# LC_BigOne_-_165_SerialIn_Register.net
KiCad netlist of a schematic drawn in Altium Designer
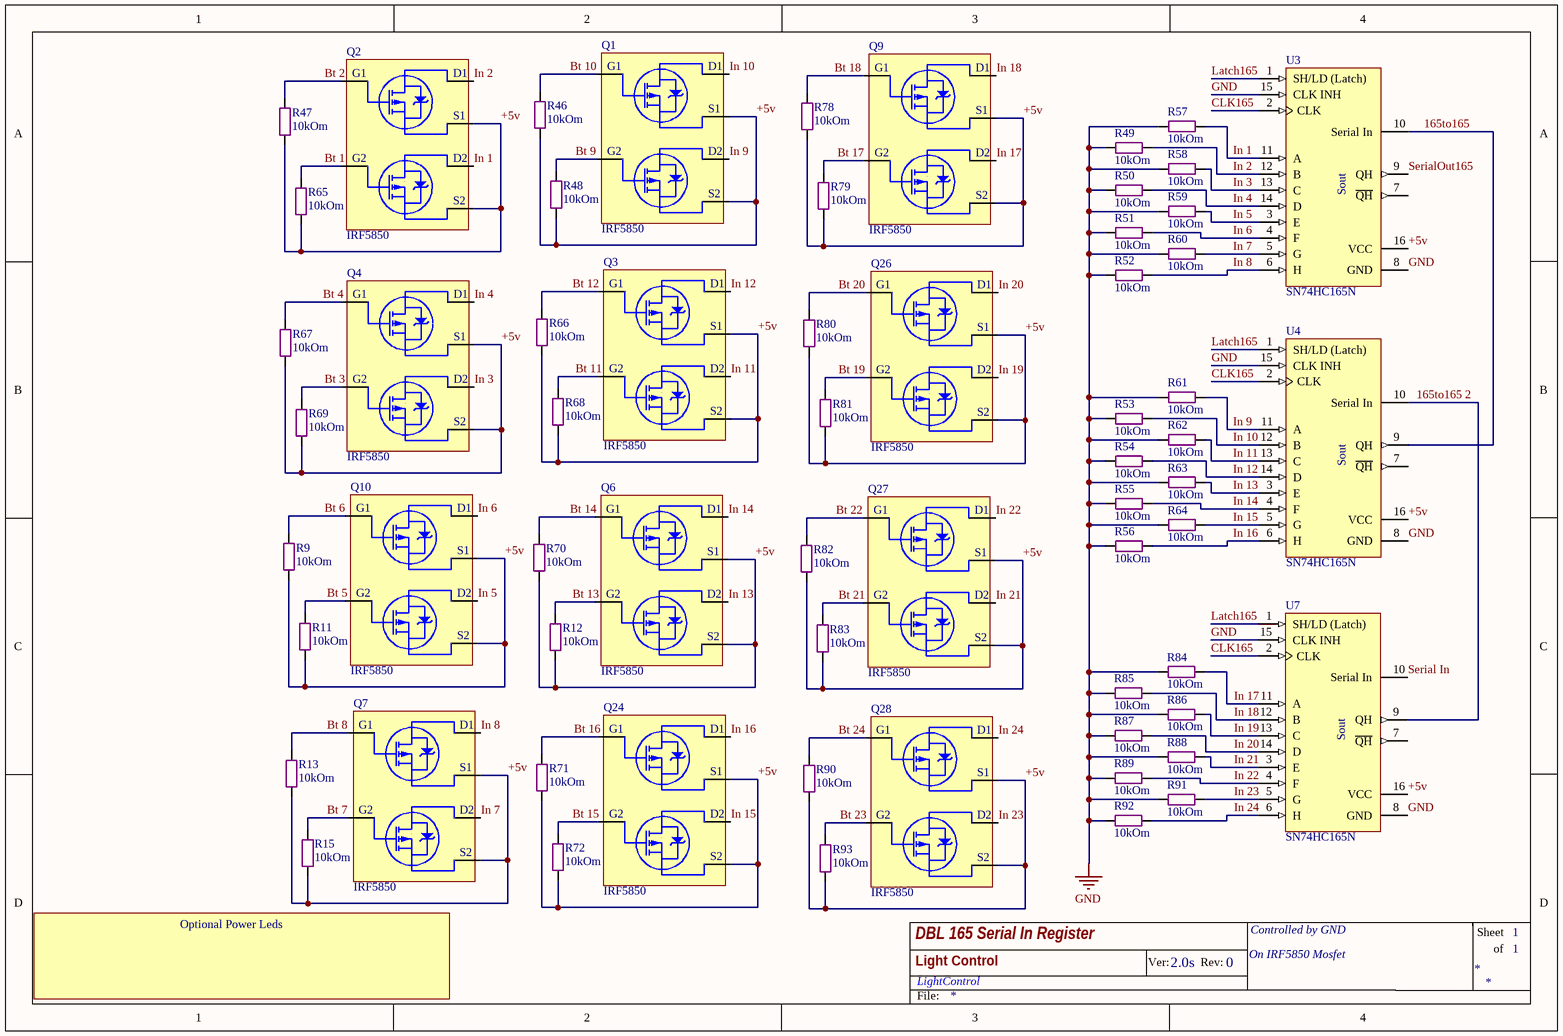
[diagram p0: LC BigOne - 165 SerialIn Register (v2).SchDoc]

(export (version "E")
  (design (tool "Eeschema 10.0.6"))
  (components
    (comp (ref "Q1")
      (value "IRF5850")
      (footprint "GeneralCases:TSOP-6")
      (description "Dual P-Ch  20V - 0.135Ω - 2.2A")
      (libsource (lib "Transistor") (part "IRF5850"))
    )
    (comp (ref "Q2")
      (value "IRF5850")
      (footprint "GeneralCases:TSOP-6")
      (description "Dual P-Ch  20V - 0.135Ω - 2.2A")
      (libsource (lib "Transistor") (part "IRF5850"))
    )
    (comp (ref "Q3")
      (value "IRF5850")
      (footprint "GeneralCases:TSOP-6")
      (description "Dual P-Ch  20V - 0.135Ω - 2.2A")
      (libsource (lib "Transistor") (part "IRF5850"))
    )
    (comp (ref "Q4")
      (value "IRF5850")
      (footprint "GeneralCases:TSOP-6")
      (description "Dual P-Ch  20V - 0.135Ω - 2.2A")
      (libsource (lib "Transistor") (part "IRF5850"))
    )
    (comp (ref "Q6")
      (value "IRF5850")
      (footprint "GeneralCases:TSOP-6")
      (description "Dual P-Ch  20V - 0.135Ω - 2.2A")
      (libsource (lib "Transistor") (part "IRF5850"))
    )
    (comp (ref "Q7")
      (value "IRF5850")
      (footprint "GeneralCases:TSOP-6")
      (description "Dual P-Ch  20V - 0.135Ω - 2.2A")
      (libsource (lib "Transistor") (part "IRF5850"))
    )
    (comp (ref "Q9")
      (value "IRF5850")
      (footprint "GeneralCases:TSOP-6")
      (description "Dual P-Ch  20V - 0.135Ω - 2.2A")
      (libsource (lib "Transistor") (part "IRF5850"))
    )
    (comp (ref "Q10")
      (value "IRF5850")
      (footprint "GeneralCases:TSOP-6")
      (description "Dual P-Ch  20V - 0.135Ω - 2.2A")
      (libsource (lib "Transistor") (part "IRF5850"))
    )
    (comp (ref "Q24")
      (value "IRF5850")
      (footprint "GeneralCases:TSOP-6")
      (description "Dual P-Ch  20V - 0.135Ω - 2.2A")
      (libsource (lib "Transistor") (part "IRF5850"))
    )
    (comp (ref "Q26")
      (value "IRF5850")
      (footprint "GeneralCases:TSOP-6")
      (description "Dual P-Ch  20V - 0.135Ω - 2.2A")
      (libsource (lib "Transistor") (part "IRF5850"))
    )
    (comp (ref "Q27")
      (value "IRF5850")
      (footprint "GeneralCases:TSOP-6")
      (description "Dual P-Ch  20V - 0.135Ω - 2.2A")
      (libsource (lib "Transistor") (part "IRF5850"))
    )
    (comp (ref "Q28")
      (value "IRF5850")
      (footprint "GeneralCases:TSOP-6")
      (description "Dual P-Ch  20V - 0.135Ω - 2.2A")
      (libsource (lib "Transistor") (part "IRF5850"))
    )
    (comp (ref "R9")
      (value "10kOm")
      (footprint "PassiveComponents:SMD 0805 (2012)")
      (libsource (lib "PassiveComponents") (part "Res All Types"))
    )
    (comp (ref "R11")
      (value "10kOm")
      (footprint "PassiveComponents:SMD 0805 (2012)")
      (libsource (lib "PassiveComponents") (part "Res All Types"))
    )
    (comp (ref "R12")
      (value "10kOm")
      (footprint "PassiveComponents:SMD 0805 (2012)")
      (libsource (lib "PassiveComponents") (part "Res All Types"))
    )
    (comp (ref "R13")
      (value "10kOm")
      (footprint "PassiveComponents:SMD 0805 (2012)")
      (libsource (lib "PassiveComponents") (part "Res All Types"))
    )
    (comp (ref "R15")
      (value "10kOm")
      (footprint "PassiveComponents:SMD 0805 (2012)")
      (libsource (lib "PassiveComponents") (part "Res All Types"))
    )
    (comp (ref "R46")
      (value "10kOm")
      (footprint "PassiveComponents:SMD 0805 (2012)")
      (libsource (lib "PassiveComponents") (part "Res All Types"))
    )
    (comp (ref "R47")
      (value "10kOm")
      (footprint "PassiveComponents:SMD 0805 (2012)")
      (libsource (lib "PassiveComponents") (part "Res All Types"))
    )
    (comp (ref "R48")
      (value "10kOm")
      (footprint "PassiveComponents:SMD 0805 (2012)")
      (libsource (lib "PassiveComponents") (part "Res All Types"))
    )
    (comp (ref "R49")
      (value "10kOm")
      (footprint "PassiveComponents:SMD 0805 (2012)")
      (libsource (lib "PassiveComponents") (part "Res All Types"))
    )
    (comp (ref "R50")
      (value "10kOm")
      (footprint "PassiveComponents:SMD 0805 (2012)")
      (libsource (lib "PassiveComponents") (part "Res All Types"))
    )
    (comp (ref "R51")
      (value "10kOm")
      (footprint "PassiveComponents:SMD 0805 (2012)")
      (libsource (lib "PassiveComponents") (part "Res All Types"))
    )
    (comp (ref "R52")
      (value "10kOm")
      (footprint "PassiveComponents:SMD 0805 (2012)")
      (libsource (lib "PassiveComponents") (part "Res All Types"))
    )
    (comp (ref "R53")
      (value "10kOm")
      (footprint "PassiveComponents:SMD 0805 (2012)")
      (libsource (lib "PassiveComponents") (part "Res All Types"))
    )
    (comp (ref "R54")
      (value "10kOm")
      (footprint "PassiveComponents:SMD 0805 (2012)")
      (libsource (lib "PassiveComponents") (part "Res All Types"))
    )
    (comp (ref "R55")
      (value "10kOm")
      (footprint "PassiveComponents:SMD 0805 (2012)")
      (libsource (lib "PassiveComponents") (part "Res All Types"))
    )
    (comp (ref "R56")
      (value "10kOm")
      (footprint "PassiveComponents:SMD 0805 (2012)")
      (libsource (lib "PassiveComponents") (part "Res All Types"))
    )
    (comp (ref "R57")
      (value "10kOm")
      (footprint "PassiveComponents:SMD 0805 (2012)")
      (libsource (lib "PassiveComponents") (part "Res All Types"))
    )
    (comp (ref "R58")
      (value "10kOm")
      (footprint "PassiveComponents:SMD 0805 (2012)")
      (libsource (lib "PassiveComponents") (part "Res All Types"))
    )
    (comp (ref "R59")
      (value "10kOm")
      (footprint "PassiveComponents:SMD 0805 (2012)")
      (libsource (lib "PassiveComponents") (part "Res All Types"))
    )
    (comp (ref "R60")
      (value "10kOm")
      (footprint "PassiveComponents:SMD 0805 (2012)")
      (libsource (lib "PassiveComponents") (part "Res All Types"))
    )
    (comp (ref "R61")
      (value "10kOm")
      (footprint "PassiveComponents:SMD 0805 (2012)")
      (libsource (lib "PassiveComponents") (part "Res All Types"))
    )
    (comp (ref "R62")
      (value "10kOm")
      (footprint "PassiveComponents:SMD 0805 (2012)")
      (libsource (lib "PassiveComponents") (part "Res All Types"))
    )
    (comp (ref "R63")
      (value "10kOm")
      (footprint "PassiveComponents:SMD 0805 (2012)")
      (libsource (lib "PassiveComponents") (part "Res All Types"))
    )
    (comp (ref "R64")
      (value "10kOm")
      (footprint "PassiveComponents:SMD 0805 (2012)")
      (libsource (lib "PassiveComponents") (part "Res All Types"))
    )
    (comp (ref "R65")
      (value "10kOm")
      (footprint "PassiveComponents:SMD 0805 (2012)")
      (libsource (lib "PassiveComponents") (part "Res All Types"))
    )
    (comp (ref "R66")
      (value "10kOm")
      (footprint "PassiveComponents:SMD 0805 (2012)")
      (libsource (lib "PassiveComponents") (part "Res All Types"))
    )
    (comp (ref "R67")
      (value "10kOm")
      (footprint "PassiveComponents:SMD 0805 (2012)")
      (libsource (lib "PassiveComponents") (part "Res All Types"))
    )
    (comp (ref "R68")
      (value "10kOm")
      (footprint "PassiveComponents:SMD 0805 (2012)")
      (libsource (lib "PassiveComponents") (part "Res All Types"))
    )
    (comp (ref "R69")
      (value "10kOm")
      (footprint "PassiveComponents:SMD 0805 (2012)")
      (libsource (lib "PassiveComponents") (part "Res All Types"))
    )
    (comp (ref "R70")
      (value "10kOm")
      (footprint "PassiveComponents:SMD 0805 (2012)")
      (libsource (lib "PassiveComponents") (part "Res All Types"))
    )
    (comp (ref "R71")
      (value "10kOm")
      (footprint "PassiveComponents:SMD 0805 (2012)")
      (libsource (lib "PassiveComponents") (part "Res All Types"))
    )
    (comp (ref "R72")
      (value "10kOm")
      (footprint "PassiveComponents:SMD 0805 (2012)")
      (libsource (lib "PassiveComponents") (part "Res All Types"))
    )
    (comp (ref "R78")
      (value "10kOm")
      (footprint "PassiveComponents:SMD 0805 (2012)")
      (libsource (lib "PassiveComponents") (part "Res All Types"))
    )
    (comp (ref "R79")
      (value "10kOm")
      (footprint "PassiveComponents:SMD 0805 (2012)")
      (libsource (lib "PassiveComponents") (part "Res All Types"))
    )
    (comp (ref "R80")
      (value "10kOm")
      (footprint "PassiveComponents:SMD 0805 (2012)")
      (libsource (lib "PassiveComponents") (part "Res All Types"))
    )
    (comp (ref "R81")
      (value "10kOm")
      (footprint "PassiveComponents:SMD 0805 (2012)")
      (libsource (lib "PassiveComponents") (part "Res All Types"))
    )
    (comp (ref "R82")
      (value "10kOm")
      (footprint "PassiveComponents:SMD 0805 (2012)")
      (libsource (lib "PassiveComponents") (part "Res All Types"))
    )
    (comp (ref "R83")
      (value "10kOm")
      (footprint "PassiveComponents:SMD 0805 (2012)")
      (libsource (lib "PassiveComponents") (part "Res All Types"))
    )
    (comp (ref "R84")
      (value "10kOm")
      (footprint "PassiveComponents:SMD 0805 (2012)")
      (libsource (lib "PassiveComponents") (part "Res All Types"))
    )
    (comp (ref "R85")
      (value "10kOm")
      (footprint "PassiveComponents:SMD 0805 (2012)")
      (libsource (lib "PassiveComponents") (part "Res All Types"))
    )
    (comp (ref "R86")
      (value "10kOm")
      (footprint "PassiveComponents:SMD 0805 (2012)")
      (libsource (lib "PassiveComponents") (part "Res All Types"))
    )
    (comp (ref "R87")
      (value "10kOm")
      (footprint "PassiveComponents:SMD 0805 (2012)")
      (libsource (lib "PassiveComponents") (part "Res All Types"))
    )
    (comp (ref "R88")
      (value "10kOm")
      (footprint "PassiveComponents:SMD 0805 (2012)")
      (libsource (lib "PassiveComponents") (part "Res All Types"))
    )
    (comp (ref "R89")
      (value "10kOm")
      (footprint "PassiveComponents:SMD 0805 (2012)")
      (libsource (lib "PassiveComponents") (part "Res All Types"))
    )
    (comp (ref "R90")
      (value "10kOm")
      (footprint "PassiveComponents:SMD 0805 (2012)")
      (libsource (lib "PassiveComponents") (part "Res All Types"))
    )
    (comp (ref "R91")
      (value "10kOm")
      (footprint "PassiveComponents:SMD 0805 (2012)")
      (libsource (lib "PassiveComponents") (part "Res All Types"))
    )
    (comp (ref "R92")
      (value "10kOm")
      (footprint "PassiveComponents:SMD 0805 (2012)")
      (libsource (lib "PassiveComponents") (part "Res All Types"))
    )
    (comp (ref "R93")
      (value "10kOm")
      (footprint "PassiveComponents:SMD 0805 (2012)")
      (libsource (lib "PassiveComponents") (part "Res All Types"))
    )
    (comp (ref "U3")
      (value "SN74HC165N")
      (footprint "GeneralCases:DIP-16")
      (description "8-Bit Parallel-Load Shift Register")
      (fields (field (name "PUBLISHER") "Altium Limited"))
      (libsource (lib "Chips") (part "SN74HC165N"))
    )
    (comp (ref "U4")
      (value "SN74HC165N")
      (footprint "GeneralCases:DIP-16")
      (description "8-Bit Parallel-Load Shift Register")
      (fields (field (name "PUBLISHER") "Altium Limited"))
      (libsource (lib "Chips") (part "SN74HC165N"))
    )
    (comp (ref "U7")
      (value "SN74HC165N")
      (footprint "GeneralCases:DIP-16")
      (description "8-Bit Parallel-Load Shift Register")
      (fields (field (name "PUBLISHER") "Altium Limited"))
      (libsource (lib "Chips") (part "SN74HC165N"))
    )
  )
  (nets
    (net (code "1") (name "/+5v") (class "Default")
      (node (ref "Q1") (pin "2") (pinfunction "S2_2") (pintype "passive"))
      (node (ref "Q1") (pin "5") (pinfunction "S1_5") (pintype "passive"))
      (node (ref "Q10") (pin "2") (pinfunction "S2_2") (pintype "passive"))
      (node (ref "Q10") (pin "5") (pinfunction "S1_5") (pintype "passive"))
      (node (ref "Q2") (pin "2") (pinfunction "S2_2") (pintype "passive"))
      (node (ref "Q2") (pin "5") (pinfunction "S1_5") (pintype "passive"))
      (node (ref "Q24") (pin "2") (pinfunction "S2_2") (pintype "passive"))
      (node (ref "Q24") (pin "5") (pinfunction "S1_5") (pintype "passive"))
      (node (ref "Q26") (pin "2") (pinfunction "S2_2") (pintype "passive"))
      (node (ref "Q26") (pin "5") (pinfunction "S1_5") (pintype "passive"))
      (node (ref "Q27") (pin "2") (pinfunction "S2_2") (pintype "passive"))
      (node (ref "Q27") (pin "5") (pinfunction "S1_5") (pintype "passive"))
      (node (ref "Q28") (pin "2") (pinfunction "S2_2") (pintype "passive"))
      (node (ref "Q28") (pin "5") (pinfunction "S1_5") (pintype "passive"))
      (node (ref "Q3") (pin "2") (pinfunction "S2_2") (pintype "passive"))
      (node (ref "Q3") (pin "5") (pinfunction "S1_5") (pintype "passive"))
      (node (ref "Q4") (pin "2") (pinfunction "S2_2") (pintype "passive"))
      (node (ref "Q4") (pin "5") (pinfunction "S1_5") (pintype "passive"))
      (node (ref "Q6") (pin "2") (pinfunction "S2_2") (pintype "passive"))
      (node (ref "Q6") (pin "5") (pinfunction "S1_5") (pintype "passive"))
      (node (ref "Q7") (pin "2") (pinfunction "S2_2") (pintype "passive"))
      (node (ref "Q7") (pin "5") (pinfunction "S1_5") (pintype "passive"))
      (node (ref "Q9") (pin "2") (pinfunction "S2_2") (pintype "passive"))
      (node (ref "Q9") (pin "5") (pinfunction "S1_5") (pintype "passive"))
      (node (ref "R11") (pin "2") (pinfunction "2_2") (pintype "passive"))
      (node (ref "R12") (pin "2") (pinfunction "2_2") (pintype "passive"))
      (node (ref "R13") (pin "2") (pinfunction "2_2") (pintype "passive"))
      (node (ref "R15") (pin "2") (pinfunction "2_2") (pintype "passive"))
      (node (ref "R46") (pin "2") (pinfunction "2_2") (pintype "passive"))
      (node (ref "R47") (pin "2") (pinfunction "2_2") (pintype "passive"))
      (node (ref "R48") (pin "2") (pinfunction "2_2") (pintype "passive"))
      (node (ref "R65") (pin "2") (pinfunction "2_2") (pintype "passive"))
      (node (ref "R66") (pin "2") (pinfunction "2_2") (pintype "passive"))
      (node (ref "R67") (pin "2") (pinfunction "2_2") (pintype "passive"))
      (node (ref "R68") (pin "2") (pinfunction "2_2") (pintype "passive"))
      (node (ref "R69") (pin "2") (pinfunction "2_2") (pintype "passive"))
      (node (ref "R70") (pin "2") (pinfunction "2_2") (pintype "passive"))
      (node (ref "R71") (pin "2") (pinfunction "2_2") (pintype "passive"))
      (node (ref "R72") (pin "2") (pinfunction "2_2") (pintype "passive"))
      (node (ref "R78") (pin "2") (pinfunction "2_2") (pintype "passive"))
      (node (ref "R79") (pin "2") (pinfunction "2_2") (pintype "passive"))
      (node (ref "R80") (pin "2") (pinfunction "2_2") (pintype "passive"))
      (node (ref "R81") (pin "2") (pinfunction "2_2") (pintype "passive"))
      (node (ref "R82") (pin "2") (pinfunction "2_2") (pintype "passive"))
      (node (ref "R83") (pin "2") (pinfunction "2_2") (pintype "passive"))
      (node (ref "R9") (pin "2") (pinfunction "2_2") (pintype "passive"))
      (node (ref "R90") (pin "2") (pinfunction "2_2") (pintype "passive"))
      (node (ref "R93") (pin "2") (pinfunction "2_2") (pintype "passive"))
      (node (ref "U3") (pin "16") (pinfunction "VCC_16") (pintype "power_in"))
      (node (ref "U4") (pin "16") (pinfunction "VCC_16") (pintype "power_in"))
      (node (ref "U7") (pin "16") (pinfunction "VCC_16") (pintype "power_in"))
    )
    (net (code "2") (name "/165to165") (class "Default")
      (node (ref "U3") (pin "10") (pinfunction "Serial_In_10") (pintype "passive"))
      (node (ref "U4") (pin "9") (pinfunction "QH_9") (pintype "output"))
    )
    (net (code "3") (name "/165to165 2") (class "Default")
      (node (ref "U4") (pin "10") (pinfunction "Serial_In_10") (pintype "passive"))
      (node (ref "U7") (pin "9") (pinfunction "QH_9") (pintype "output"))
    )
    (net (code "4") (name "/Bt 1") (class "Default")
      (node (ref "Q2") (pin "3") (pinfunction "G2_3") (pintype "passive"))
      (node (ref "R65") (pin "1") (pinfunction "1_1") (pintype "passive"))
    )
    (net (code "5") (name "/Bt 2") (class "Default")
      (node (ref "Q2") (pin "1") (pinfunction "G1_1") (pintype "passive"))
      (node (ref "R47") (pin "1") (pinfunction "1_1") (pintype "passive"))
    )
    (net (code "6") (name "/Bt 3") (class "Default")
      (node (ref "Q4") (pin "3") (pinfunction "G2_3") (pintype "passive"))
      (node (ref "R69") (pin "1") (pinfunction "1_1") (pintype "passive"))
    )
    (net (code "7") (name "/Bt 4") (class "Default")
      (node (ref "Q4") (pin "1") (pinfunction "G1_1") (pintype "passive"))
      (node (ref "R67") (pin "1") (pinfunction "1_1") (pintype "passive"))
    )
    (net (code "8") (name "/Bt 5") (class "Default")
      (node (ref "Q10") (pin "3") (pinfunction "G2_3") (pintype "passive"))
      (node (ref "R11") (pin "1") (pinfunction "1_1") (pintype "passive"))
    )
    (net (code "9") (name "/Bt 6") (class "Default")
      (node (ref "Q10") (pin "1") (pinfunction "G1_1") (pintype "passive"))
      (node (ref "R9") (pin "1") (pinfunction "1_1") (pintype "passive"))
    )
    (net (code "10") (name "/Bt 7") (class "Default")
      (node (ref "Q7") (pin "3") (pinfunction "G2_3") (pintype "passive"))
      (node (ref "R15") (pin "1") (pinfunction "1_1") (pintype "passive"))
    )
    (net (code "11") (name "/Bt 8") (class "Default")
      (node (ref "Q7") (pin "1") (pinfunction "G1_1") (pintype "passive"))
      (node (ref "R13") (pin "1") (pinfunction "1_1") (pintype "passive"))
    )
    (net (code "12") (name "/Bt 9") (class "Default")
      (node (ref "Q1") (pin "3") (pinfunction "G2_3") (pintype "passive"))
      (node (ref "R48") (pin "1") (pinfunction "1_1") (pintype "passive"))
    )
    (net (code "13") (name "/Bt 10") (class "Default")
      (node (ref "Q1") (pin "1") (pinfunction "G1_1") (pintype "passive"))
      (node (ref "R46") (pin "1") (pinfunction "1_1") (pintype "passive"))
    )
    (net (code "14") (name "/Bt 11") (class "Default")
      (node (ref "Q3") (pin "3") (pinfunction "G2_3") (pintype "passive"))
      (node (ref "R68") (pin "1") (pinfunction "1_1") (pintype "passive"))
    )
    (net (code "15") (name "/Bt 12") (class "Default")
      (node (ref "Q3") (pin "1") (pinfunction "G1_1") (pintype "passive"))
      (node (ref "R66") (pin "1") (pinfunction "1_1") (pintype "passive"))
    )
    (net (code "16") (name "/Bt 13") (class "Default")
      (node (ref "Q6") (pin "3") (pinfunction "G2_3") (pintype "passive"))
      (node (ref "R12") (pin "1") (pinfunction "1_1") (pintype "passive"))
    )
    (net (code "17") (name "/Bt 14") (class "Default")
      (node (ref "Q6") (pin "1") (pinfunction "G1_1") (pintype "passive"))
      (node (ref "R70") (pin "1") (pinfunction "1_1") (pintype "passive"))
    )
    (net (code "18") (name "/Bt 15") (class "Default")
      (node (ref "Q24") (pin "3") (pinfunction "G2_3") (pintype "passive"))
      (node (ref "R72") (pin "1") (pinfunction "1_1") (pintype "passive"))
    )
    (net (code "19") (name "/Bt 16") (class "Default")
      (node (ref "Q24") (pin "1") (pinfunction "G1_1") (pintype "passive"))
      (node (ref "R71") (pin "1") (pinfunction "1_1") (pintype "passive"))
    )
    (net (code "20") (name "/Bt 17") (class "Default")
      (node (ref "Q9") (pin "3") (pinfunction "G2_3") (pintype "passive"))
      (node (ref "R79") (pin "1") (pinfunction "1_1") (pintype "passive"))
    )
    (net (code "21") (name "/Bt 18") (class "Default")
      (node (ref "Q9") (pin "1") (pinfunction "G1_1") (pintype "passive"))
      (node (ref "R78") (pin "1") (pinfunction "1_1") (pintype "passive"))
    )
    (net (code "22") (name "/Bt 19") (class "Default")
      (node (ref "Q26") (pin "3") (pinfunction "G2_3") (pintype "passive"))
      (node (ref "R81") (pin "1") (pinfunction "1_1") (pintype "passive"))
    )
    (net (code "23") (name "/Bt 20") (class "Default")
      (node (ref "Q26") (pin "1") (pinfunction "G1_1") (pintype "passive"))
      (node (ref "R80") (pin "1") (pinfunction "1_1") (pintype "passive"))
    )
    (net (code "24") (name "/Bt 21") (class "Default")
      (node (ref "Q27") (pin "3") (pinfunction "G2_3") (pintype "passive"))
      (node (ref "R83") (pin "1") (pinfunction "1_1") (pintype "passive"))
    )
    (net (code "25") (name "/Bt 22") (class "Default")
      (node (ref "Q27") (pin "1") (pinfunction "G1_1") (pintype "passive"))
      (node (ref "R82") (pin "1") (pinfunction "1_1") (pintype "passive"))
    )
    (net (code "26") (name "/Bt 23") (class "Default")
      (node (ref "Q28") (pin "3") (pinfunction "G2_3") (pintype "passive"))
      (node (ref "R93") (pin "1") (pinfunction "1_1") (pintype "passive"))
    )
    (net (code "27") (name "/Bt 24") (class "Default")
      (node (ref "Q28") (pin "1") (pinfunction "G1_1") (pintype "passive"))
      (node (ref "R90") (pin "1") (pinfunction "1_1") (pintype "passive"))
    )
    (net (code "28") (name "/CLK165") (class "Default")
      (node (ref "U3") (pin "2") (pinfunction "CLK_2") (pintype "input"))
      (node (ref "U4") (pin "2") (pinfunction "CLK_2") (pintype "input"))
      (node (ref "U7") (pin "2") (pinfunction "CLK_2") (pintype "input"))
    )
    (net (code "29") (name "/In 1") (class "Default")
      (node (ref "Q2") (pin "4") (pinfunction "D2_4") (pintype "passive"))
      (node (ref "R57") (pin "2") (pinfunction "2_2") (pintype "passive"))
      (node (ref "U3") (pin "11") (pinfunction "A_11") (pintype "input"))
    )
    (net (code "30") (name "/In 2") (class "Default")
      (node (ref "Q2") (pin "6") (pinfunction "D1_6") (pintype "passive"))
      (node (ref "R49") (pin "2") (pinfunction "2_2") (pintype "passive"))
      (node (ref "U3") (pin "12") (pinfunction "B_12") (pintype "input"))
    )
    (net (code "31") (name "/In 3") (class "Default")
      (node (ref "Q4") (pin "4") (pinfunction "D2_4") (pintype "passive"))
      (node (ref "R58") (pin "2") (pinfunction "2_2") (pintype "passive"))
      (node (ref "U3") (pin "13") (pinfunction "C_13") (pintype "input"))
    )
    (net (code "32") (name "/In 4") (class "Default")
      (node (ref "Q4") (pin "6") (pinfunction "D1_6") (pintype "passive"))
      (node (ref "R50") (pin "2") (pinfunction "2_2") (pintype "passive"))
      (node (ref "U3") (pin "14") (pinfunction "D_14") (pintype "input"))
    )
    (net (code "33") (name "/In 5") (class "Default")
      (node (ref "Q10") (pin "4") (pinfunction "D2_4") (pintype "passive"))
      (node (ref "R59") (pin "2") (pinfunction "2_2") (pintype "passive"))
      (node (ref "U3") (pin "3") (pinfunction "E_3") (pintype "input"))
    )
    (net (code "34") (name "/In 6") (class "Default")
      (node (ref "Q10") (pin "6") (pinfunction "D1_6") (pintype "passive"))
      (node (ref "R51") (pin "2") (pinfunction "2_2") (pintype "passive"))
      (node (ref "U3") (pin "4") (pinfunction "F_4") (pintype "input"))
    )
    (net (code "35") (name "/In 7") (class "Default")
      (node (ref "Q7") (pin "4") (pinfunction "D2_4") (pintype "passive"))
      (node (ref "R60") (pin "2") (pinfunction "2_2") (pintype "passive"))
      (node (ref "U3") (pin "5") (pinfunction "G_5") (pintype "input"))
    )
    (net (code "36") (name "/In 8") (class "Default")
      (node (ref "Q7") (pin "6") (pinfunction "D1_6") (pintype "passive"))
      (node (ref "R52") (pin "2") (pinfunction "2_2") (pintype "passive"))
      (node (ref "U3") (pin "6") (pinfunction "H_6") (pintype "input"))
    )
    (net (code "37") (name "/In 9") (class "Default")
      (node (ref "Q1") (pin "4") (pinfunction "D2_4") (pintype "passive"))
      (node (ref "R61") (pin "2") (pinfunction "2_2") (pintype "passive"))
      (node (ref "U4") (pin "11") (pinfunction "A_11") (pintype "input"))
    )
    (net (code "38") (name "/In 10") (class "Default")
      (node (ref "Q1") (pin "6") (pinfunction "D1_6") (pintype "passive"))
      (node (ref "R53") (pin "2") (pinfunction "2_2") (pintype "passive"))
      (node (ref "U4") (pin "12") (pinfunction "B_12") (pintype "input"))
    )
    (net (code "39") (name "/In 11") (class "Default")
      (node (ref "Q3") (pin "4") (pinfunction "D2_4") (pintype "passive"))
      (node (ref "R62") (pin "2") (pinfunction "2_2") (pintype "passive"))
      (node (ref "U4") (pin "13") (pinfunction "C_13") (pintype "input"))
    )
    (net (code "40") (name "/In 12") (class "Default")
      (node (ref "Q3") (pin "6") (pinfunction "D1_6") (pintype "passive"))
      (node (ref "R54") (pin "2") (pinfunction "2_2") (pintype "passive"))
      (node (ref "U4") (pin "14") (pinfunction "D_14") (pintype "input"))
    )
    (net (code "41") (name "/In 13") (class "Default")
      (node (ref "Q6") (pin "4") (pinfunction "D2_4") (pintype "passive"))
      (node (ref "R63") (pin "2") (pinfunction "2_2") (pintype "passive"))
      (node (ref "U4") (pin "3") (pinfunction "E_3") (pintype "input"))
    )
    (net (code "42") (name "/In 14") (class "Default")
      (node (ref "Q6") (pin "6") (pinfunction "D1_6") (pintype "passive"))
      (node (ref "R55") (pin "2") (pinfunction "2_2") (pintype "passive"))
      (node (ref "U4") (pin "4") (pinfunction "F_4") (pintype "input"))
    )
    (net (code "43") (name "/In 15") (class "Default")
      (node (ref "Q24") (pin "4") (pinfunction "D2_4") (pintype "passive"))
      (node (ref "R64") (pin "2") (pinfunction "2_2") (pintype "passive"))
      (node (ref "U4") (pin "5") (pinfunction "G_5") (pintype "input"))
    )
    (net (code "44") (name "/In 16") (class "Default")
      (node (ref "Q24") (pin "6") (pinfunction "D1_6") (pintype "passive"))
      (node (ref "R56") (pin "2") (pinfunction "2_2") (pintype "passive"))
      (node (ref "U4") (pin "6") (pinfunction "H_6") (pintype "input"))
    )
    (net (code "45") (name "/In 17") (class "Default")
      (node (ref "Q9") (pin "4") (pinfunction "D2_4") (pintype "passive"))
      (node (ref "R84") (pin "2") (pinfunction "2_2") (pintype "passive"))
      (node (ref "U7") (pin "11") (pinfunction "A_11") (pintype "input"))
    )
    (net (code "46") (name "/In 18") (class "Default")
      (node (ref "Q9") (pin "6") (pinfunction "D1_6") (pintype "passive"))
      (node (ref "R85") (pin "2") (pinfunction "2_2") (pintype "passive"))
      (node (ref "U7") (pin "12") (pinfunction "B_12") (pintype "input"))
    )
    (net (code "47") (name "/In 19") (class "Default")
      (node (ref "Q26") (pin "4") (pinfunction "D2_4") (pintype "passive"))
      (node (ref "R86") (pin "2") (pinfunction "2_2") (pintype "passive"))
      (node (ref "U7") (pin "13") (pinfunction "C_13") (pintype "input"))
    )
    (net (code "48") (name "/In 20") (class "Default")
      (node (ref "Q26") (pin "6") (pinfunction "D1_6") (pintype "passive"))
      (node (ref "R87") (pin "2") (pinfunction "2_2") (pintype "passive"))
      (node (ref "U7") (pin "14") (pinfunction "D_14") (pintype "input"))
    )
    (net (code "49") (name "/In 21") (class "Default")
      (node (ref "Q27") (pin "4") (pinfunction "D2_4") (pintype "passive"))
      (node (ref "R88") (pin "2") (pinfunction "2_2") (pintype "passive"))
      (node (ref "U7") (pin "3") (pinfunction "E_3") (pintype "input"))
    )
    (net (code "50") (name "/In 22") (class "Default")
      (node (ref "Q27") (pin "6") (pinfunction "D1_6") (pintype "passive"))
      (node (ref "R89") (pin "2") (pinfunction "2_2") (pintype "passive"))
      (node (ref "U7") (pin "4") (pinfunction "F_4") (pintype "input"))
    )
    (net (code "51") (name "/In 23") (class "Default")
      (node (ref "Q28") (pin "4") (pinfunction "D2_4") (pintype "passive"))
      (node (ref "R91") (pin "2") (pinfunction "2_2") (pintype "passive"))
      (node (ref "U7") (pin "5") (pinfunction "G_5") (pintype "input"))
    )
    (net (code "52") (name "/In 24") (class "Default")
      (node (ref "Q28") (pin "6") (pinfunction "D1_6") (pintype "passive"))
      (node (ref "R92") (pin "2") (pinfunction "2_2") (pintype "passive"))
      (node (ref "U7") (pin "6") (pinfunction "H_6") (pintype "input"))
    )
    (net (code "53") (name "/Latch165") (class "Default")
      (node (ref "U3") (pin "1") (pinfunction "SH/LD_(Latch)_1") (pintype "input"))
      (node (ref "U4") (pin "1") (pinfunction "SH/LD_(Latch)_1") (pintype "input"))
      (node (ref "U7") (pin "1") (pinfunction "SH/LD_(Latch)_1") (pintype "input"))
    )
    (net (code "54") (name "/Serial In") (class "Default")
      (node (ref "U7") (pin "10") (pinfunction "Serial_In_10") (pintype "passive"))
    )
    (net (code "55") (name "/SerialOut165") (class "Default")
      (node (ref "U3") (pin "9") (pinfunction "QH_9") (pintype "output"))
    )
    (net (code "56") (name "GND") (class "Default")
      (node (ref "R49") (pin "1") (pinfunction "1_1") (pintype "passive"))
      (node (ref "R50") (pin "1") (pinfunction "1_1") (pintype "passive"))
      (node (ref "R51") (pin "1") (pinfunction "1_1") (pintype "passive"))
      (node (ref "R52") (pin "1") (pinfunction "1_1") (pintype "passive"))
      (node (ref "R53") (pin "1") (pinfunction "1_1") (pintype "passive"))
      (node (ref "R54") (pin "1") (pinfunction "1_1") (pintype "passive"))
      (node (ref "R55") (pin "1") (pinfunction "1_1") (pintype "passive"))
      (node (ref "R56") (pin "1") (pinfunction "1_1") (pintype "passive"))
      (node (ref "R57") (pin "1") (pinfunction "1_1") (pintype "passive"))
      (node (ref "R58") (pin "1") (pinfunction "1_1") (pintype "passive"))
      (node (ref "R59") (pin "1") (pinfunction "1_1") (pintype "passive"))
      (node (ref "R60") (pin "1") (pinfunction "1_1") (pintype "passive"))
      (node (ref "R61") (pin "1") (pinfunction "1_1") (pintype "passive"))
      (node (ref "R62") (pin "1") (pinfunction "1_1") (pintype "passive"))
      (node (ref "R63") (pin "1") (pinfunction "1_1") (pintype "passive"))
      (node (ref "R64") (pin "1") (pinfunction "1_1") (pintype "passive"))
      (node (ref "R84") (pin "1") (pinfunction "1_1") (pintype "passive"))
      (node (ref "R85") (pin "1") (pinfunction "1_1") (pintype "passive"))
      (node (ref "R86") (pin "1") (pinfunction "1_1") (pintype "passive"))
      (node (ref "R87") (pin "1") (pinfunction "1_1") (pintype "passive"))
      (node (ref "R88") (pin "1") (pinfunction "1_1") (pintype "passive"))
      (node (ref "R89") (pin "1") (pinfunction "1_1") (pintype "passive"))
      (node (ref "R91") (pin "1") (pinfunction "1_1") (pintype "passive"))
      (node (ref "R92") (pin "1") (pinfunction "1_1") (pintype "passive"))
      (node (ref "U3") (pin "15") (pinfunction "CLK_INH_15") (pintype "input"))
      (node (ref "U3") (pin "8") (pinfunction "GND_8") (pintype "power_in"))
      (node (ref "U4") (pin "15") (pinfunction "CLK_INH_15") (pintype "input"))
      (node (ref "U4") (pin "8") (pinfunction "GND_8") (pintype "power_in"))
      (node (ref "U7") (pin "15") (pinfunction "CLK_INH_15") (pintype "input"))
      (node (ref "U7") (pin "8") (pinfunction "GND_8") (pintype "power_in"))
    )
    (net (code "57") (name "unconnected-(U3-~{QH}-Pad7)") (class "Default")
      (node (ref "U3") (pin "7") (pinfunction "~{QH}_7") (pintype "output"))
    )
    (net (code "58") (name "unconnected-(U4-~{QH}-Pad7)") (class "Default")
      (node (ref "U4") (pin "7") (pinfunction "~{QH}_7") (pintype "output"))
    )
    (net (code "59") (name "unconnected-(U7-~{QH}-Pad7)") (class "Default")
      (node (ref "U7") (pin "7") (pinfunction "~{QH}_7") (pintype "output"))
    )
  )
)
